# circuit_breaker.net
KiCad netlist of a schematic drawn in Altium Designer
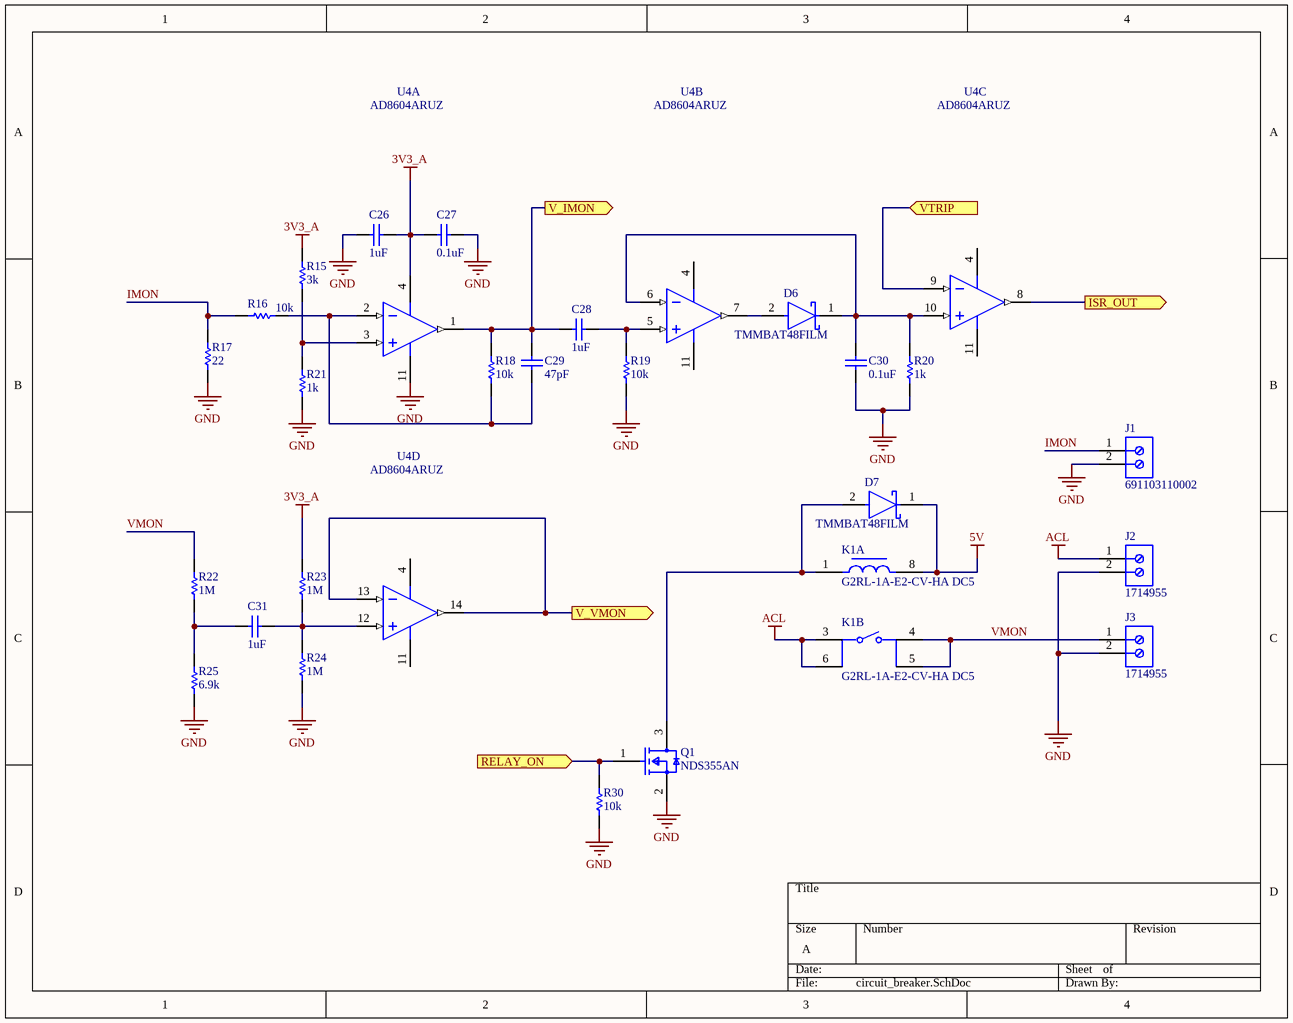
[diagram p0: circuit_breaker.SchDoc]

(export (version "E")
  (design (tool "Eeschema 10.0.6"))
  (components
    (comp (ref "C26")
      (value "1uF")
      (footprint "0603C")
      (fields
        (field (name "MANUFACTURER") "Kyocera AVX")
        (field (name "MANUFACTURER PART NUMBER") "0603YD105MAT2A")
        (field (name "TOLERANCE") "20%")
      )
      (libsource (lib "MB398B1") (part "0603YD105MAT2A"))
    )
    (comp (ref "C27")
      (value "0.1uF")
      (footprint "0603C")
      (description "Cap Ceramic 0.1uF 25V X7R 10% Pad SMD 0603 125C Automotive T/R")
      (fields
        (field (name "MANUFACTURER") "Kyocera AVX")
        (field (name "MANUFACTURER PART NUMBER") "06033C104K4T4A")
      )
      (libsource (lib "MB398B1") (part "06033C104K4T4A"))
    )
    (comp (ref "C28")
      (value "1uF")
      (footprint "0603C")
      (fields
        (field (name "MANUFACTURER") "Kyocera AVX")
        (field (name "MANUFACTURER PART NUMBER") "0603YD105MAT2A")
        (field (name "TOLERANCE") "20%")
      )
      (libsource (lib "MB398B1") (part "0603YD105MAT2A"))
    )
    (comp (ref "C29")
      (value "47pF")
      (footprint "0603C")
      (description "Cap Ceramic 47pF 50V C0G 10% SMD 0603 125C Paper T/R")
      (fields
        (field (name "MANUFACTURER") "Yageo")
        (field (name "MANUFACTURER PART NUMBER") "CC0603KRNPO9BN470")
      )
      (libsource (lib "MB398B1") (part "CC0603KRNPO9BN470"))
    )
    (comp (ref "C30")
      (value "0.1uF")
      (footprint "0603C")
      (description "Cap Ceramic 0.1uF 25V X7R 10% Pad SMD 0603 125C Automotive T/R")
      (fields
        (field (name "MANUFACTURER") "Kyocera AVX")
        (field (name "MANUFACTURER PART NUMBER") "06033C104K4T4A")
      )
      (libsource (lib "MB398B1") (part "06033C104K4T4A"))
    )
    (comp (ref "C31")
      (value "1uF")
      (footprint "0603C")
      (fields
        (field (name "MANUFACTURER") "Kyocera AVX")
        (field (name "MANUFACTURER PART NUMBER") "0603YD105MAT2A")
        (field (name "TOLERANCE") "20%")
      )
      (libsource (lib "MB398B1") (part "0603YD105MAT2A"))
    )
    (comp (ref "D6")
      (value "TMMBAT48FILM")
      (footprint "FP-MINIMELF-MFG")
      (description "DIODE SCHOTTKY 40V 350MA MINMELF")
      (fields
        (field (name "MANUFACTURER") "STMicroelectronics")
        (field (name "OCTOPART") "https://octopart.com/tmmbat48film-stmicroelectronics-324396")
      )
      (libsource (lib "Altium Content Vault") (part "1d6ec82d83fb6aee721767c19dac4b9"))
    )
    (comp (ref "D7")
      (value "TMMBAT48FILM")
      (footprint "FP-MINIMELF-MFG")
      (description "DIODE SCHOTTKY 40V 350MA MINMELF")
      (fields
        (field (name "MANUFACTURER") "STMicroelectronics")
        (field (name "OCTOPART") "https://octopart.com/tmmbat48film-stmicroelectronics-324396")
      )
      (libsource (lib "Altium Content Vault") (part "1d6ec82d83fb6aee721767c19dac4b9"))
    )
    (comp (ref "J1")
      (value "691103110002")
      (footprint "691103110002")
      (description "Series 1031 - 3.50 mm Horizontal Entry Modular with Pressure Clamp WR-TBL, 2 pin")
      (fields (field (name "MANUFACTURER") "Wurth Elektronik") (field (name "PUBLISHER") "WurthElektronik"))
      (libsource (lib "Altium Content Vault") (part "WE-CN-1P-F-TB2"))
    )
    (comp (ref "J2")
      (value "1714955")
      (footprint "PHOE-1714955_V")
      (description "PC Terminal Block, Pitch 6.35 mm, 1 x 2 Position, Height 21.5 mm, Tail Lenght 5.1 mm, RoHS, Bulk")
      (fields (field (name "MANUFACTURER") "Phoenix Contact"))
      (libsource (lib "Altium Content Vault") (part "CN-1P-F-TB2"))
    )
    (comp (ref "J3")
      (value "1714955")
      (footprint "PHOE-1714955_V")
      (description "PC Terminal Block, Pitch 6.35 mm, 1 x 2 Position, Height 21.5 mm, Tail Lenght 5.1 mm, RoHS, Bulk")
      (fields (field (name "MANUFACTURER") "Phoenix Contact"))
      (libsource (lib "Altium Content Vault") (part "CN-1P-F-TB2"))
    )
    (comp (ref "K1")
      (value "G2RL-1A-E2-CV-HA DC5")
      (footprint "FP-G2RL-1A-E2-CV-HA-MFG")
      (description "General Purpose Relay SPST-NO (1 Form A) 5VDC Coil Through Hole")
      (fields (field (name "OCTOPART") "https://octopart.com/g2rl-1a-e2-cv-ha+dc5-omron-100806975"))
      (libsource (lib "Altium Content Vault") (part "c586dc1e264205e8028f8e3b5ca9a49"))
    )
    (comp (ref "Q1")
      (value "NDS355AN")
      (footprint "FP-527AG-01-IPC_C")
      (description "MOSFET N-CH 30V 1.7A SSOT3")
      (fields
        (field (name "OCTOPART") "https://octopart.com/nds355an-on+semiconductor-84330922")
        (field (name "MANUFACTURER") "ON Semiconductor")
      )
      (libsource (lib "Altium Content Vault") (part "3b9c635fedb024a5347a57b145af9cc"))
    )
    (comp (ref "R15")
      (value "3k")
      (footprint "0603R")
      (description "Resistor, SMD 220 Ohm 0603  ±  0.1 %, ERA3AEB221V, Panasonic Automotive & Industrial Systems")
      (fields (field (name "Comment") "ERA-3APB302V"))
      (libsource (lib "MB398B1") (part "ERA-3APB302V"))
    )
    (comp (ref "R16")
      (value "10k")
      (footprint "0603R")
      (description "Resistor, SMD 10 kOhm 0603  ±  0.1 %, ERA3ARB103V, Panasonic Automotive & Industrial Systems")
      (fields
        (field (name "MANUFACTURER") "Panasonic")
        (field (name "MANUFACTURER PART NUMBER") "ERA-3ARB103V")
        (field (name "PUBLISHER") "Altium Limited")
      )
      (libsource (lib "MB398B1") (part "ERA-3ARB103V"))
    )
    (comp (ref "R17")
      (value "22")
      (footprint "0603R")
      (description "Resistor, SMD 220 Ohm 0603  ±  0.1 %, ERA3AEB221V, Panasonic Automotive & Industrial Systems")
      (fields (field (name "Comment") "RMCF0603JT22R0"))
      (libsource (lib "MB398B1") (part "RMCF0603JT22R0"))
    )
    (comp (ref "R18")
      (value "10k")
      (footprint "0603R")
      (description "Resistor, SMD 10 kOhm 0603  ±  0.1 %, ERA3ARB103V, Panasonic Automotive & Industrial Systems")
      (fields
        (field (name "MANUFACTURER") "Panasonic")
        (field (name "MANUFACTURER PART NUMBER") "ERA-3ARB103V")
        (field (name "PUBLISHER") "Altium Limited")
      )
      (libsource (lib "MB398B1") (part "ERA-3ARB103V"))
    )
    (comp (ref "R19")
      (value "10k")
      (footprint "0603R")
      (description "Resistor, SMD 10 kOhm 0603  ±  0.1 %, ERA3ARB103V, Panasonic Automotive & Industrial Systems")
      (fields
        (field (name "MANUFACTURER") "Panasonic")
        (field (name "MANUFACTURER PART NUMBER") "ERA-3ARB103V")
        (field (name "PUBLISHER") "Altium Limited")
      )
      (libsource (lib "MB398B1") (part "ERA-3ARB103V"))
    )
    (comp (ref "R20")
      (value "1k")
      (footprint "0603R")
      (description "PANASONIC - ERJ-PB3D1001V - CHIP RES, THICK FILM, 1K, 0.2W, 0603")
      (fields
        (field (name "MANUFACTURER") "Panasonic")
        (field (name "MANUFACTURER PART NUMBER") "ERJ-PB3D1001V")
      )
      (libsource (lib "MB398B1") (part "ERJ-PB3D1001V"))
    )
    (comp (ref "R21")
      (value "1k")
      (footprint "0603R")
      (description "PANASONIC - ERJ-PB3D1001V - CHIP RES, THICK FILM, 1K, 0.2W, 0603")
      (fields
        (field (name "MANUFACTURER") "Panasonic")
        (field (name "MANUFACTURER PART NUMBER") "ERJ-PB3D1001V")
      )
      (libsource (lib "MB398B1") (part "ERJ-PB3D1001V"))
    )
    (comp (ref "R22")
      (value "1M")
      (footprint "0603R")
      (description "Resistor, SMD 220 Ohm 0603  ±  0.1 %, ERA3AEB221V, Panasonic Automotive & Industrial Systems")
      (fields (field (name "Comment") "ERJ-3GEYJ105V"))
      (libsource (lib "MB398B1") (part "ERJ-3GEYJ105V"))
    )
    (comp (ref "R23")
      (value "1M")
      (footprint "0603R")
      (description "Resistor, SMD 220 Ohm 0603  ±  0.1 %, ERA3AEB221V, Panasonic Automotive & Industrial Systems")
      (fields (field (name "Comment") "ERJ-3GEYJ105V"))
      (libsource (lib "MB398B1") (part "ERJ-3GEYJ105V"))
    )
    (comp (ref "R24")
      (value "1M")
      (footprint "0603R")
      (description "Resistor, SMD 220 Ohm 0603  ±  0.1 %, ERA3AEB221V, Panasonic Automotive & Industrial Systems")
      (fields (field (name "Comment") "ERJ-3GEYJ105V"))
      (libsource (lib "MB398B1") (part "ERJ-3GEYJ105V"))
    )
    (comp (ref "R25")
      (value "6.9k")
      (footprint "0603R")
      (description "Resistor, SMD 220 Ohm 0603  ±  0.1 %, ERA3AEB221V, Panasonic Automotive & Industrial Systems")
      (fields (field (name "Comment") "ERJ-3EKF1692V"))
      (libsource (lib "MB398B1") (part "ERJ-3EKF1692V"))
    )
    (comp (ref "R30")
      (value "10k")
      (footprint "0603R")
      (description "Resistor, SMD 10 kOhm 0603  ±  0.1 %, ERA3ARB103V, Panasonic Automotive & Industrial Systems")
      (fields
        (field (name "MANUFACTURER") "Panasonic")
        (field (name "MANUFACTURER PART NUMBER") "ERA-3ARB103V")
        (field (name "PUBLISHER") "Altium Limited")
      )
      (libsource (lib "MB398B1") (part "ERA-3ARB103V"))
    )
    (comp (ref "U4")
      (value "AD8604ARUZ")
      (footprint "ADI-RU-14_M")
      (fields (field (name "MANUFACTURER") "Analog Devices") (field (name "GENERIC PART NUMBER") "AD8604"))
      (libsource (lib "Altium Content Vault") (part "ADI-ADxxxx_OPxxxx-X-14"))
    )
  )
  (nets
    (net (code "1") (name "/IMON") (class "Default")
      (node (ref "J1") (pin "1") (pinfunction "1_1") (pintype "passive"))
      (node (ref "R16") (pin "1") (pinfunction "1_1") (pintype "passive"))
      (node (ref "R17") (pin "2") (pinfunction "2_2") (pintype "passive"))
    )
    (net (code "2") (name "/ISR_OUT") (class "Default")
      (node (ref "U4") (pin "8") (pinfunction "OUT_C_8") (pintype "output"))
    )
    (net (code "3") (name "/RELAY_ON") (class "Default")
      (node (ref "Q1") (pin "1") (pinfunction "G_1") (pintype "passive"))
      (node (ref "R30") (pin "2") (pinfunction "2_2") (pintype "passive"))
    )
    (net (code "4") (name "/VMON") (class "Default")
      (node (ref "J3") (pin "1") (pinfunction "1_1") (pintype "passive"))
      (node (ref "K1") (pin "4") (pinfunction "4_4") (pintype "passive"))
      (node (ref "K1") (pin "5") (pinfunction "5_5") (pintype "passive"))
      (node (ref "R22") (pin "2") (pinfunction "2_2") (pintype "passive"))
    )
    (net (code "5") (name "/VTRIP") (class "Default")
      (node (ref "U4") (pin "9") (pinfunction "-IN_C_9") (pintype "input"))
    )
    (net (code "6") (name "/V_IMON") (class "Default")
      (node (ref "C28") (pin "1") (pinfunction "1_1") (pintype "passive"))
      (node (ref "C29") (pin "2") (pinfunction "2_2") (pintype "passive"))
      (node (ref "R18") (pin "2") (pinfunction "2_2") (pintype "passive"))
      (node (ref "U4") (pin "1") (pinfunction "OUT_A_1") (pintype "output"))
    )
    (net (code "7") (name "/V_VMON") (class "Default")
      (node (ref "U4") (pin "13") (pinfunction "-IN_D_13") (pintype "input"))
      (node (ref "U4") (pin "14") (pinfunction "OUT_D_14") (pintype "output"))
    )
    (net (code "8") (name "3V3_A") (class "Default")
      (node (ref "C26") (pin "2") (pinfunction "2_2") (pintype "passive"))
      (node (ref "C27") (pin "1") (pinfunction "1_1") (pintype "passive"))
      (node (ref "R15") (pin "2") (pinfunction "2_2") (pintype "passive"))
      (node (ref "R23") (pin "2") (pinfunction "2_2") (pintype "passive"))
      (node (ref "U4") (pin "4") (pinfunction "+V_4") (pintype "power_in"))
    )
    (net (code "9") (name "5V") (class "Default")
      (node (ref "D7") (pin "1") (pinfunction "C_1") (pintype "passive"))
      (node (ref "K1") (pin "8") (pinfunction "8_8") (pintype "passive"))
    )
    (net (code "10") (name "ACL") (class "Default")
      (node (ref "J2") (pin "1") (pinfunction "1_1") (pintype "passive"))
      (node (ref "K1") (pin "3") (pinfunction "3_3") (pintype "passive"))
      (node (ref "K1") (pin "6") (pinfunction "6_6") (pintype "passive"))
    )
    (net (code "11") (name "GND") (class "Default")
      (node (ref "C26") (pin "1") (pinfunction "1_1") (pintype "passive"))
      (node (ref "C27") (pin "2") (pinfunction "2_2") (pintype "passive"))
      (node (ref "C30") (pin "1") (pinfunction "1_1") (pintype "passive"))
      (node (ref "J1") (pin "2") (pinfunction "2_2") (pintype "passive"))
      (node (ref "J2") (pin "2") (pinfunction "2_2") (pintype "passive"))
      (node (ref "J3") (pin "2") (pinfunction "2_2") (pintype "passive"))
      (node (ref "Q1") (pin "2") (pinfunction "S_2") (pintype "passive"))
      (node (ref "R17") (pin "1") (pinfunction "1_1") (pintype "passive"))
      (node (ref "R19") (pin "1") (pinfunction "1_1") (pintype "passive"))
      (node (ref "R20") (pin "1") (pinfunction "1_1") (pintype "passive"))
      (node (ref "R21") (pin "1") (pinfunction "1_1") (pintype "passive"))
      (node (ref "R24") (pin "1") (pinfunction "1_1") (pintype "passive"))
      (node (ref "R25") (pin "1") (pinfunction "1_1") (pintype "passive"))
      (node (ref "R30") (pin "1") (pinfunction "1_1") (pintype "passive"))
      (node (ref "U4") (pin "11") (pinfunction "-V_11") (pintype "power_in"))
    )
    (net (code "12") (name "Net-(C31-Pad1)") (class "Default")
      (node (ref "C31") (pin "1") (pinfunction "1_1") (pintype "passive"))
      (node (ref "R22") (pin "1") (pinfunction "1_1") (pintype "passive"))
      (node (ref "R25") (pin "2") (pinfunction "2_2") (pintype "passive"))
    )
    (net (code "13") (name "Net-(D6-A)") (class "Default")
      (node (ref "D6") (pin "2") (pinfunction "A_2") (pintype "passive"))
      (node (ref "U4") (pin "7") (pinfunction "OUT_B_7") (pintype "output"))
    )
    (net (code "14") (name "Net-(D6-C)") (class "Default")
      (node (ref "C30") (pin "2") (pinfunction "2_2") (pintype "passive"))
      (node (ref "D6") (pin "1") (pinfunction "C_1") (pintype "passive"))
      (node (ref "R20") (pin "2") (pinfunction "2_2") (pintype "passive"))
      (node (ref "U4") (pin "10") (pinfunction "+IN_C_10") (pintype "input"))
      (node (ref "U4") (pin "6") (pinfunction "-IN_B_6") (pintype "input"))
    )
    (net (code "15") (name "Net-(D7-A)") (class "Default")
      (node (ref "D7") (pin "2") (pinfunction "A_2") (pintype "passive"))
      (node (ref "K1") (pin "1") (pinfunction "1_1") (pintype "passive"))
      (node (ref "Q1") (pin "3") (pinfunction "D_3") (pintype "passive"))
    )
    (net (code "16") (name "Net-(U4A-+IN_A)") (class "Default")
      (node (ref "R15") (pin "1") (pinfunction "1_1") (pintype "passive"))
      (node (ref "R21") (pin "2") (pinfunction "2_2") (pintype "passive"))
      (node (ref "U4") (pin "3") (pinfunction "+IN_A_3") (pintype "input"))
    )
    (net (code "17") (name "Net-(U4A--IN_A)") (class "Default")
      (node (ref "C29") (pin "1") (pinfunction "1_1") (pintype "passive"))
      (node (ref "R16") (pin "2") (pinfunction "2_2") (pintype "passive"))
      (node (ref "R18") (pin "1") (pinfunction "1_1") (pintype "passive"))
      (node (ref "U4") (pin "2") (pinfunction "-IN_A_2") (pintype "input"))
    )
    (net (code "18") (name "Net-(U4B-+IN_B)") (class "Default")
      (node (ref "C28") (pin "2") (pinfunction "2_2") (pintype "passive"))
      (node (ref "R19") (pin "2") (pinfunction "2_2") (pintype "passive"))
      (node (ref "U4") (pin "5") (pinfunction "+IN_B_5") (pintype "input"))
    )
    (net (code "19") (name "Net-(U4D-+IN_D)") (class "Default")
      (node (ref "C31") (pin "2") (pinfunction "2_2") (pintype "passive"))
      (node (ref "R23") (pin "1") (pinfunction "1_1") (pintype "passive"))
      (node (ref "R24") (pin "2") (pinfunction "2_2") (pintype "passive"))
      (node (ref "U4") (pin "12") (pinfunction "+IN_D_12") (pintype "input"))
    )
    (net (code "20") (name "unconnected-(U4B-+V-Pad4)") (class "Default")
      (node (ref "U4") (pin "4") (pinfunction "+V_4") (pintype "power_in"))
    )
    (net (code "21") (name "unconnected-(U4B--V-Pad11)") (class "Default")
      (node (ref "U4") (pin "11") (pinfunction "-V_11") (pintype "power_in"))
    )
    (net (code "22") (name "unconnected-(U4C-+V-Pad4)") (class "Default")
      (node (ref "U4") (pin "4") (pinfunction "+V_4") (pintype "power_in"))
    )
    (net (code "23") (name "unconnected-(U4C--V-Pad11)") (class "Default")
      (node (ref "U4") (pin "11") (pinfunction "-V_11") (pintype "power_in"))
    )
    (net (code "24") (name "unconnected-(U4D-+V-Pad4)") (class "Default")
      (node (ref "U4") (pin "4") (pinfunction "+V_4") (pintype "power_in"))
    )
    (net (code "25") (name "unconnected-(U4D--V-Pad11)") (class "Default")
      (node (ref "U4") (pin "11") (pinfunction "-V_11") (pintype "power_in"))
    )
  )
)
